# WIRELESS.net
KiCad netlist of a schematic drawn in Altium Designer
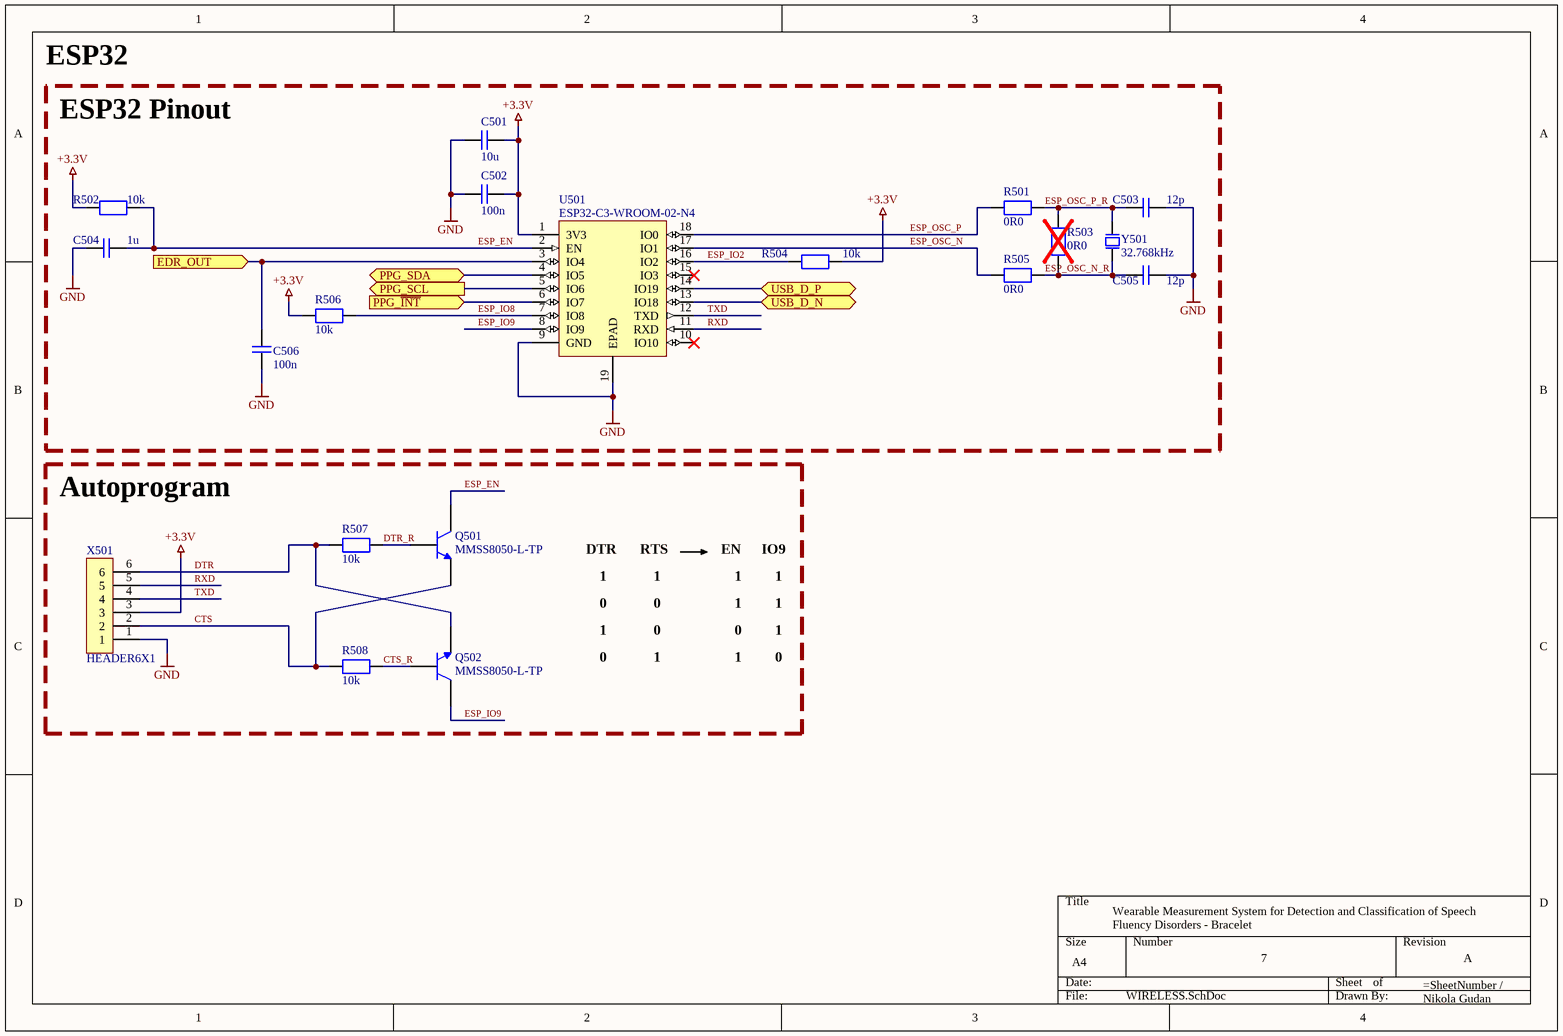
[diagram p0: WIRELESS.SchDoc]

(export (version "E")
  (design (tool "Eeschema 10.0.6"))
  (components
    (comp (ref "C501")
      (value "10u")
      (footprint "CAPC0603")
      (description "Ceramic capacitor, 10uF,  25V, X5R")
      (fields (field (name "MFR") "TAIYO YUDEN") (field (name "CHECKED") "Yes"))
      (libsource (lib "NG_Passive") (part "CAPC0603-10u-20"))
    )
    (comp (ref "C502")
      (value "100n")
      (footprint "CAPC0603")
      (description "Ceramic capacitor, 100nF,  50V, X7R")
      (fields (field (name "MFR") "KEMET") (field (name "CHECKED") "Yes"))
      (libsource (lib "NG_Passive") (part "CAPC0603-100n-10"))
    )
    (comp (ref "C503")
      (value "12p")
      (footprint "CAPC0603")
      (description "Ceramic capacitor, 12pF,  100V, C0G")
      (fields (field (name "MFR") "Murata Electronics") (field (name "CHECKED") "Yes"))
      (libsource (lib "NG_Passive") (part "CAPC0603-12p-1"))
    )
    (comp (ref "C504")
      (value "1u")
      (footprint "CAPC0603")
      (description "Ceramic capacitor, 1uF,  50V, X5R")
      (fields (field (name "MFR") "Murata Electronics") (field (name "CHECKED") "Yes"))
      (libsource (lib "NG_Passive") (part "CAPC0603-1u-10"))
    )
    (comp (ref "C505")
      (value "12p")
      (footprint "CAPC0603")
      (description "Ceramic capacitor, 12pF,  100V, C0G")
      (fields (field (name "MFR") "Murata Electronics") (field (name "CHECKED") "Yes"))
      (libsource (lib "NG_Passive") (part "CAPC0603-12p-1"))
    )
    (comp (ref "C506")
      (value "100n")
      (footprint "CAPC0603")
      (description "Ceramic capacitor, 100nF,  50V, X7R")
      (fields (field (name "MFR") "KEMET") (field (name "CHECKED") "Yes"))
      (libsource (lib "NG_Passive") (part "CAPC0603-100n-10"))
    )
    (comp (ref "Q501")
      (value "MMSS8050-L-TP")
      (footprint "SOT190P240X290-3")
      (description "BJT, NPN, 25V, 1.5A")
      (fields (field (name "MFR") "Micro Commercial Components (MCC)") (field (name "CHECKED") "No"))
      (libsource (lib "NG_Active") (part "MMSS8050-L-TP"))
    )
    (comp (ref "Q502")
      (value "MMSS8050-L-TP")
      (footprint "SOT190P240X290-3")
      (description "BJT, NPN, 25V, 1.5A")
      (fields (field (name "MFR") "Micro Commercial Components (MCC)") (field (name "CHECKED") "No"))
      (libsource (lib "NG_Active") (part "MMSS8050-L-TP"))
    )
    (comp (ref "R501")
      (value "0R0")
      (footprint "RESC0603")
      (description "Thick film resistor, 0Ohms, 100mW")
      (fields (field (name "MFR") "YAGEO") (field (name "CHECKED") "Yes"))
      (libsource (lib "NG_Passive") (part "RES0603-0R0-1"))
    )
    (comp (ref "R502")
      (value "10k")
      (footprint "RESC0603")
      (description "Thick film resistor, 10kOhm, 100mW")
      (fields (field (name "MFR") "YAGEO") (field (name "CHECKED") "Yes"))
      (libsource (lib "NG_Passive") (part "RES0603-10k-1"))
    )
    (comp (ref "R503")
      (value "0R0")
      (footprint "RESC0603")
      (description "Thick film resistor, 0Ohms, 100mW")
      (fields (field (name "MFR") "YAGEO") (field (name "CHECKED") "Yes"))
      (libsource (lib "NG_Passive") (part "RES0603-0R0-1"))
    )
    (comp (ref "R504")
      (value "10k")
      (footprint "RESC0603")
      (description "Thick film resistor, 10kOhm, 100mW")
      (fields (field (name "MFR") "YAGEO") (field (name "CHECKED") "Yes"))
      (libsource (lib "NG_Passive") (part "RES0603-10k-1"))
    )
    (comp (ref "R505")
      (value "0R0")
      (footprint "RESC0603")
      (description "Thick film resistor, 0Ohms, 100mW")
      (fields (field (name "MFR") "YAGEO") (field (name "CHECKED") "Yes"))
      (libsource (lib "NG_Passive") (part "RES0603-0R0-1"))
    )
    (comp (ref "R506")
      (value "10k")
      (footprint "RESC0603")
      (description "Thick film resistor, 10kOhm, 100mW")
      (fields (field (name "MFR") "YAGEO") (field (name "CHECKED") "Yes"))
      (libsource (lib "NG_Passive") (part "RES0603-10k-1"))
    )
    (comp (ref "R507")
      (value "10k")
      (footprint "RESC0603")
      (description "Thick film resistor, 10kOhm, 100mW")
      (fields (field (name "MFR") "YAGEO") (field (name "CHECKED") "Yes"))
      (libsource (lib "NG_Passive") (part "RES0603-10k-1"))
    )
    (comp (ref "R508")
      (value "10k")
      (footprint "RESC0603")
      (description "Thick film resistor, 10kOhm, 100mW")
      (fields (field (name "MFR") "YAGEO") (field (name "CHECKED") "Yes"))
      (libsource (lib "NG_Passive") (part "RES0603-10k-1"))
    )
    (comp (ref "U501")
      (value "ESP32-C3-WROOM-02-N4")
      (footprint "ESP32-C3-WROOM-02-N4")
      (description "RF transceiver module, Bluetooth, WiFi")
      (fields (field (name "MFR") "Espressif Systems") (field (name "CHECKED") "Yes"))
      (libsource (lib "NG_Digital") (part "ESP32-C3-WROOM-02-N4"))
    )
    (comp (ref "X501")
      (value "HEADER6X1")
      (footprint "HDR6W64P254_6X1_1524X254X1150")
      (description "Pin header, 6x1, 100mil pitch")
      (fields (field (name "MFR") "Adam Tech") (field (name "CHECKED") "Yes"))
      (libsource (lib "NG_Mechanical") (part "HEADER6X1"))
    )
    (comp (ref "Y501")
      (value "32.768kHz")
      (footprint "XTAL320X150X80")
      (description "Crystal, 32.768Hz, 9pF, 50kOhms")
      (fields (field (name "MFR") "Seiko Epson") (field (name "CHECKED") "Yes"))
      (libsource (lib "NG_Passive") (part "FC-135R 32.7680KA-AC"))
    )
  )
  (nets
    (net (code "1") (name "+3.3V") (class "Default")
      (node (ref "C501") (pin "2") (pinfunction "2_2") (pintype "passive"))
      (node (ref "C502") (pin "2") (pinfunction "2_2") (pintype "passive"))
      (node (ref "R502") (pin "2") (pinfunction "2_2") (pintype "passive"))
      (node (ref "R504") (pin "1") (pinfunction "1_1") (pintype "passive"))
      (node (ref "R506") (pin "2") (pinfunction "2_2") (pintype "passive"))
      (node (ref "U501") (pin "1") (pinfunction "3V3_1") (pintype "power_in"))
      (node (ref "X501") (pin "3") (pinfunction "3_3") (pintype "passive"))
    )
    (net (code "2") (name "/CTS") (class "Default")
      (node (ref "Q501") (pin "2") (pinfunction "E_2") (pintype "passive"))
      (node (ref "R508") (pin "1") (pinfunction "1_1") (pintype "passive"))
      (node (ref "X501") (pin "2") (pinfunction "2_2") (pintype "passive"))
    )
    (net (code "3") (name "/CTS_R") (class "Default")
      (node (ref "Q502") (pin "1") (pinfunction "B_1") (pintype "passive"))
      (node (ref "R508") (pin "2") (pinfunction "2_2") (pintype "passive"))
    )
    (net (code "4") (name "/DTR") (class "Default")
      (node (ref "Q502") (pin "2") (pinfunction "E_2") (pintype "passive"))
      (node (ref "R507") (pin "1") (pinfunction "1_1") (pintype "passive"))
      (node (ref "X501") (pin "6") (pinfunction "6_6") (pintype "passive"))
    )
    (net (code "5") (name "/DTR_R") (class "Default")
      (node (ref "Q501") (pin "1") (pinfunction "B_1") (pintype "passive"))
      (node (ref "R507") (pin "2") (pinfunction "2_2") (pintype "passive"))
    )
    (net (code "6") (name "/EDR_OUT") (class "Default")
      (node (ref "C506") (pin "2") (pinfunction "2_2") (pintype "passive"))
      (node (ref "U501") (pin "3") (pinfunction "IO4_3") (pintype "bidirectional"))
    )
    (net (code "7") (name "/ESP_EN") (class "Default")
      (node (ref "C504") (pin "1") (pinfunction "1_1") (pintype "passive"))
      (node (ref "Q501") (pin "3") (pinfunction "C_3") (pintype "passive"))
      (node (ref "R502") (pin "1") (pinfunction "1_1") (pintype "passive"))
      (node (ref "U501") (pin "2") (pinfunction "EN_2") (pintype "input"))
    )
    (net (code "8") (name "/ESP_IO2") (class "Default")
      (node (ref "R504") (pin "2") (pinfunction "2_2") (pintype "passive"))
      (node (ref "U501") (pin "16") (pinfunction "IO2_16") (pintype "bidirectional"))
    )
    (net (code "9") (name "/ESP_IO8") (class "Default")
      (node (ref "R506") (pin "1") (pinfunction "1_1") (pintype "passive"))
      (node (ref "U501") (pin "7") (pinfunction "IO8_7") (pintype "bidirectional"))
    )
    (net (code "10") (name "/ESP_IO9") (class "Default")
      (node (ref "Q502") (pin "3") (pinfunction "C_3") (pintype "passive"))
      (node (ref "U501") (pin "8") (pinfunction "IO9_8") (pintype "bidirectional"))
    )
    (net (code "11") (name "/ESP_OSC_N") (class "Default")
      (node (ref "R505") (pin "1") (pinfunction "1_1") (pintype "passive"))
      (node (ref "U501") (pin "17") (pinfunction "IO1_17") (pintype "bidirectional"))
    )
    (net (code "12") (name "/ESP_OSC_N_R") (class "Default")
      (node (ref "C505") (pin "1") (pinfunction "1_1") (pintype "passive"))
      (node (ref "R503") (pin "1") (pinfunction "1_1") (pintype "passive"))
      (node (ref "R505") (pin "2") (pinfunction "2_2") (pintype "passive"))
      (node (ref "Y501") (pin "1") (pinfunction "1_1") (pintype "passive"))
    )
    (net (code "13") (name "/ESP_OSC_P") (class "Default")
      (node (ref "R501") (pin "1") (pinfunction "1_1") (pintype "passive"))
      (node (ref "U501") (pin "18") (pinfunction "IO0_18") (pintype "bidirectional"))
    )
    (net (code "14") (name "/ESP_OSC_P_R") (class "Default")
      (node (ref "C503") (pin "1") (pinfunction "1_1") (pintype "passive"))
      (node (ref "R501") (pin "2") (pinfunction "2_2") (pintype "passive"))
      (node (ref "R503") (pin "2") (pinfunction "2_2") (pintype "passive"))
      (node (ref "Y501") (pin "2") (pinfunction "2_2") (pintype "passive"))
    )
    (net (code "15") (name "/PPG_SCL") (class "Default")
      (node (ref "U501") (pin "5") (pinfunction "IO6_5") (pintype "bidirectional"))
    )
    (net (code "16") (name "/PPG_SDA") (class "Default")
      (node (ref "U501") (pin "4") (pinfunction "IO5_4") (pintype "bidirectional"))
    )
    (net (code "17") (name "/PPG_~{INT}") (class "Default")
      (node (ref "U501") (pin "6") (pinfunction "IO7_6") (pintype "bidirectional"))
    )
    (net (code "18") (name "/RXD") (class "Default")
      (node (ref "U501") (pin "11") (pinfunction "RXD_11") (pintype "input"))
      (node (ref "X501") (pin "5") (pinfunction "5_5") (pintype "passive"))
    )
    (net (code "19") (name "/TXD") (class "Default")
      (node (ref "U501") (pin "12") (pinfunction "TXD_12") (pintype "output"))
      (node (ref "X501") (pin "4") (pinfunction "4_4") (pintype "passive"))
    )
    (net (code "20") (name "/USB_D_N") (class "Default")
      (node (ref "U501") (pin "13") (pinfunction "IO18_13") (pintype "bidirectional"))
    )
    (net (code "21") (name "/USB_D_P") (class "Default")
      (node (ref "U501") (pin "14") (pinfunction "IO19_14") (pintype "bidirectional"))
    )
    (net (code "22") (name "GND") (class "Default")
      (node (ref "C501") (pin "1") (pinfunction "1_1") (pintype "passive"))
      (node (ref "C502") (pin "1") (pinfunction "1_1") (pintype "passive"))
      (node (ref "C503") (pin "2") (pinfunction "2_2") (pintype "passive"))
      (node (ref "C504") (pin "2") (pinfunction "2_2") (pintype "passive"))
      (node (ref "C505") (pin "2") (pinfunction "2_2") (pintype "passive"))
      (node (ref "C506") (pin "1") (pinfunction "1_1") (pintype "passive"))
      (node (ref "U501") (pin "19") (pinfunction "EPAD_19") (pintype "power_in"))
      (node (ref "U501") (pin "9") (pinfunction "GND_9") (pintype "power_in"))
      (node (ref "X501") (pin "1") (pinfunction "1_1") (pintype "passive"))
    )
    (net (code "23") (name "unconnected-(U501-IO3-Pad15)") (class "Default")
      (node (ref "U501") (pin "15") (pinfunction "IO3_15") (pintype "bidirectional+no_connect"))
    )
    (net (code "24") (name "unconnected-(U501-IO10-Pad10)") (class "Default")
      (node (ref "U501") (pin "10") (pinfunction "IO10_10") (pintype "bidirectional+no_connect"))
    )
  )
)
